# MAIN.net
KiCad netlist of a schematic drawn in Altium Designer
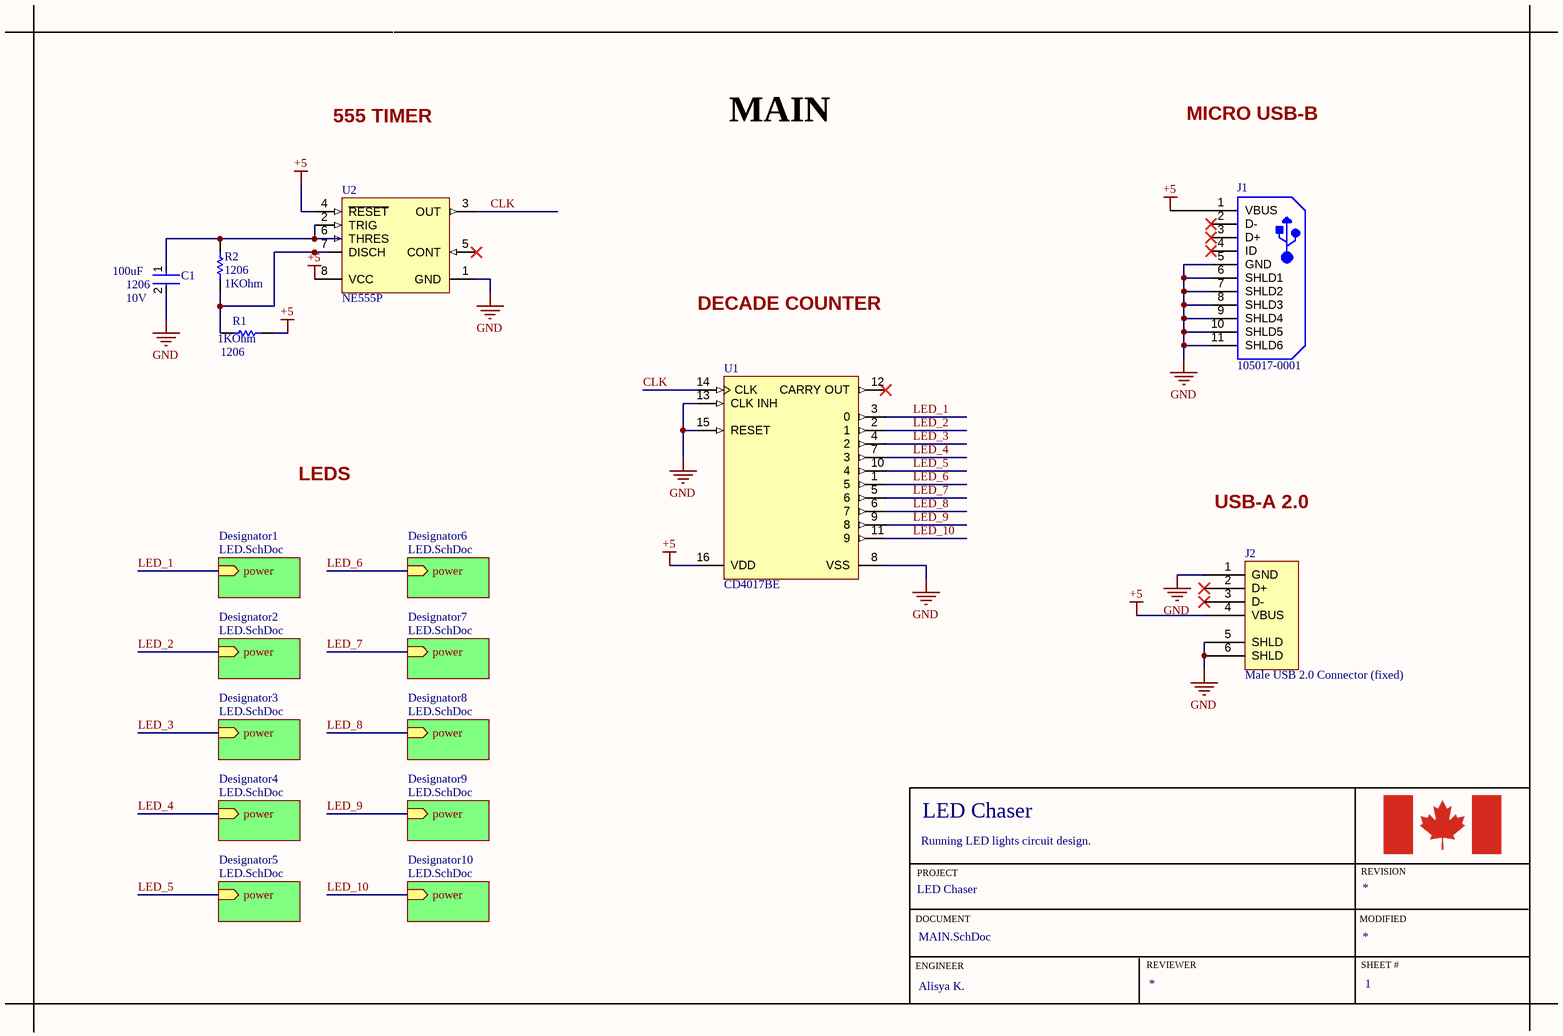
[diagram p0: MAIN.SchDoc]

(export (version "E")
  (design (tool "Eeschema 10.0.6"))
  (components
    (comp (ref "C1")
      (value "C3216X5R1A107M160AC")
      (footprint "FP-C3216-160-0_3-IPC_C")
      (description "Multilayer Ceramic Capacitors 100uF ±20% 10V X5R SMD 1206")
      (fields
        (field (name "CAPACITANCE") "100uF")
        (field (name "VOLTAGE") "10V")
        (field (name "TOLERANCE") "20%")
        (field (name "CASE/PACKAGE") "1206")
      )
      (libsource (lib "Altium Content Vault") (part "02cd4be3c70576c341d710602a673aa"))
    )
    (comp (ref "J1")
      (value "105017-0001")
      (footprint "USB-MICRO-B_V")
      (fields (field (name "MANUFACTURER") "Molex"))
      (libsource (lib "Altium Content Vault") (part "USB-5-6SHLD"))
    )
    (comp (ref "J2")
      (value "Male USB 2.0 Connector (fixed)")
      (footprint "MOLX-480-37-1000_V")
      (libsource (lib "pcb stuff") (part "Male USB 2.0 Connector (fixed)-Symbol-1"))
    )
    (comp (ref "R1")
      (value "CRCW12061K00FKEA")
      (footprint "RESC3216X60X45ML15T20")
      (description "Chip Resistor, 1 KOhm, +/- 1%, 0.25 W, -55 to 155 degC, 1206 (3216 Metric), RoHS, Tape and Reel")
      (fields
        (field (name "CASE CODE (IMPERIAL)") "1206")
        (field (name "MANUFACTURER") "Vishay Semiconductor")
        (field (name "TOLERANCE") "1%")
        (field (name "RESISTANCE") "1KOhm")
      )
      (libsource (lib "Altium Content Vault") (part "RES-2"))
    )
    (comp (ref "R2")
      (value "CRCW12061K00FKEA")
      (footprint "RESC3216X60X45ML15T20")
      (description "Chip Resistor, 1 KOhm, +/- 1%, 0.25 W, -55 to 155 degC, 1206 (3216 Metric), RoHS, Tape and Reel")
      (fields
        (field (name "CASE/PACKAGE") "1206")
        (field (name "MANUFACTURER") "Vishay Semiconductor")
        (field (name "TOLERANCE") "1%")
        (field (name "RESISTANCE") "1KOhm")
      )
      (libsource (lib "Altium Content Vault") (part "RES-2"))
    )
    (comp (ref "U1")
      (value "CD4017BE")
      (footprint "N0016A")
      (description "CMOS Decade Counter with 10 Decoded Outputs, N0016A, TUBE")
      (fields
        (field (name "MANUFACTURER") "Texas Instruments")
        (field (name "GENERIC PART NUMBER") "CD4017B")
      )
      (libsource (lib "Altium Content Vault") (part "TI-CD4017B-16"))
    )
    (comp (ref "U2")
      (value "NE555P")
      (footprint "P0008A")
      (description "Precision Timer, 4.5 to 16 V, 0 to 70 degC, 8-Pin DIP, Pb-Free, Tube")
      (fields (field (name "MANUFACTURER") "TexasInstruments"))
      (libsource (lib "Altium Content Vault") (part "TI-NE555-P8"))
    )
  )
  (nets
    (net (code "1") (name "+5") (class "Default")
      (node (ref "J1") (pin "1") (pinfunction "VBUS_1") (pintype "passive"))
      (node (ref "J2") (pin "4") (pinfunction "VBUS_4") (pintype "passive"))
      (node (ref "R1") (pin "2") (pinfunction "2_2") (pintype "passive"))
      (node (ref "U1") (pin "16") (pinfunction "VDD_16") (pintype "power_in"))
      (node (ref "U2") (pin "4") (pinfunction "~{RESET}_4") (pintype "input"))
      (node (ref "U2") (pin "8") (pinfunction "VCC_8") (pintype "power_in"))
    )
    (net (code "2") (name "/CLK") (class "Default")
      (node (ref "U1") (pin "14") (pinfunction "CLK_14") (pintype "input"))
      (node (ref "U2") (pin "3") (pinfunction "OUT_3") (pintype "output"))
    )
    (net (code "3") (name "/LED_1") (class "Default")
      (node (ref "U1") (pin "3") (pinfunction "0_3") (pintype "output"))
    )
    (net (code "4") (name "/LED_2") (class "Default")
      (node (ref "U1") (pin "2") (pinfunction "1_2") (pintype "output"))
    )
    (net (code "5") (name "/LED_3") (class "Default")
      (node (ref "U1") (pin "4") (pinfunction "2_4") (pintype "output"))
    )
    (net (code "6") (name "/LED_4") (class "Default")
      (node (ref "U1") (pin "7") (pinfunction "3_7") (pintype "output"))
    )
    (net (code "7") (name "/LED_5") (class "Default")
      (node (ref "U1") (pin "10") (pinfunction "4_10") (pintype "output"))
    )
    (net (code "8") (name "/LED_6") (class "Default")
      (node (ref "U1") (pin "1") (pinfunction "5_1") (pintype "output"))
    )
    (net (code "9") (name "/LED_7") (class "Default")
      (node (ref "U1") (pin "5") (pinfunction "6_5") (pintype "output"))
    )
    (net (code "10") (name "/LED_8") (class "Default")
      (node (ref "U1") (pin "6") (pinfunction "7_6") (pintype "output"))
    )
    (net (code "11") (name "/LED_9") (class "Default")
      (node (ref "U1") (pin "9") (pinfunction "8_9") (pintype "output"))
    )
    (net (code "12") (name "/LED_10") (class "Default")
      (node (ref "U1") (pin "11") (pinfunction "9_11") (pintype "output"))
    )
    (net (code "13") (name "GND") (class "Default")
      (node (ref "C1") (pin "2") (pinfunction "2_2") (pintype "passive"))
      (node (ref "J1") (pin "10") (pinfunction "SHLD5_10") (pintype "passive"))
      (node (ref "J1") (pin "11") (pinfunction "SHLD6_11") (pintype "passive"))
      (node (ref "J1") (pin "5") (pinfunction "GND_5") (pintype "passive"))
      (node (ref "J1") (pin "6") (pinfunction "SHLD1_6") (pintype "passive"))
      (node (ref "J1") (pin "7") (pinfunction "SHLD2_7") (pintype "passive"))
      (node (ref "J1") (pin "8") (pinfunction "SHLD3_8") (pintype "passive"))
      (node (ref "J1") (pin "9") (pinfunction "SHLD4_9") (pintype "passive"))
      (node (ref "J2") (pin "1") (pinfunction "GND_1") (pintype "passive"))
      (node (ref "J2") (pin "5") (pinfunction "SHLD_5") (pintype "passive"))
      (node (ref "J2") (pin "6") (pinfunction "SHLD_6") (pintype "passive"))
      (node (ref "U1") (pin "13") (pinfunction "CLK_INH_13") (pintype "input"))
      (node (ref "U1") (pin "15") (pinfunction "RESET_15") (pintype "input"))
      (node (ref "U1") (pin "8") (pinfunction "VSS_8") (pintype "power_in"))
      (node (ref "U2") (pin "1") (pinfunction "GND_1") (pintype "power_in"))
    )
    (net (code "14") (name "Net-(U2-DISCH)") (class "Default")
      (node (ref "R1") (pin "1") (pinfunction "1_1") (pintype "passive"))
      (node (ref "R2") (pin "2") (pinfunction "2_2") (pintype "passive"))
      (node (ref "U2") (pin "7") (pinfunction "DISCH_7") (pintype "open_collector"))
    )
    (net (code "15") (name "Net-(U2-THRES)") (class "Default")
      (node (ref "C1") (pin "1") (pinfunction "1_1") (pintype "passive"))
      (node (ref "R2") (pin "1") (pinfunction "1_1") (pintype "passive"))
      (node (ref "U2") (pin "2") (pinfunction "TRIG_2") (pintype "input"))
      (node (ref "U2") (pin "6") (pinfunction "THRES_6") (pintype "input"))
    )
    (net (code "16") (name "unconnected-(J1-D+-Pad3)") (class "Default")
      (node (ref "J1") (pin "3") (pinfunction "D+_3") (pintype "passive+no_connect"))
    )
    (net (code "17") (name "unconnected-(J1-D--Pad2)") (class "Default")
      (node (ref "J1") (pin "2") (pinfunction "D-_2") (pintype "passive+no_connect"))
    )
    (net (code "18") (name "unconnected-(J1-ID-Pad4)") (class "Default")
      (node (ref "J1") (pin "4") (pinfunction "ID_4") (pintype "passive+no_connect"))
    )
    (net (code "19") (name "unconnected-(J2-D+-Pad2)") (class "Default")
      (node (ref "J2") (pin "2") (pinfunction "D+_2") (pintype "passive+no_connect"))
    )
    (net (code "20") (name "unconnected-(J2-D--Pad3)") (class "Default")
      (node (ref "J2") (pin "3") (pinfunction "D-_3") (pintype "passive+no_connect"))
    )
    (net (code "21") (name "unconnected-(U1-CARRY_OUT-Pad12)") (class "Default")
      (node (ref "U1") (pin "12") (pinfunction "CARRY_OUT_12") (pintype "output+no_connect"))
    )
    (net (code "22") (name "unconnected-(U2-CONT-Pad5)") (class "Default")
      (node (ref "U2") (pin "5") (pinfunction "CONT_5") (pintype "input+no_connect"))
    )
  )
)
